# fpc.net
KiCad netlist of a schematic drawn in Altium Designer
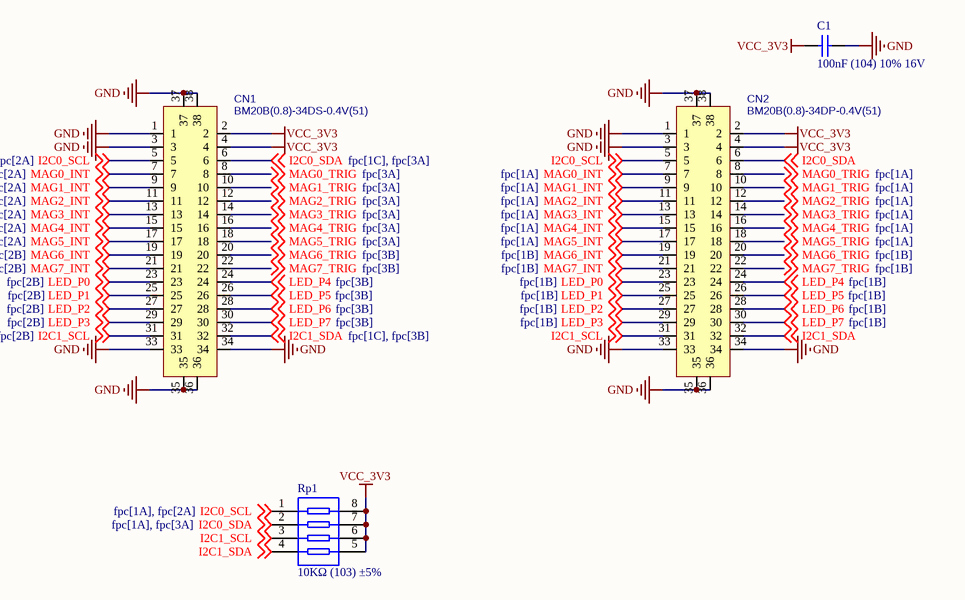
[diagram p0: fpc.SchDoc]

(export (version "E")
  (design (tool "Eeschema 10.0.6"))
  (components
    (comp (ref "C1")
      (value "100nF (104) 10% 16V")
      (footprint "LC-0402_C_NOSILK")
      (description "贴片电容")
      (libsource (lib "Miscellaneous Devices LC") (part "0402 100nF (104) 10% 16V"))
    )
    (comp (ref "CN1")
      (value "BM20B(0.8)-34DS-0.4V(51)")
      (footprint "CONN-SMD_34P-P0.40_BM20B-0.8-34DS-0.4V-51")
      (description "0.4mm BTB连接器-34P 母")
      (fields (field (name "BOM_SUPPLIER PART") "C424541") (field (name "CONTRIBUTOR") "LCSC"))
      (libsource (lib "merci") (part "BM20B(0.8)-34DS-0.4V(51)"))
    )
    (comp (ref "CN2")
      (value "BM20B(0.8)-34DP-0.4V(51)")
      (footprint "CONN-SMD_34P-P0.40_BM20B-0.8-34DP-0.4V-51")
      (description "0.4mm BTB连接器-34P 公")
      (fields (field (name "BOM_SUPPLIER PART") "C424540") (field (name "CONTRIBUTOR") "LCSC"))
      (libsource (lib "merci") (part "BM20B(0.8)-34DP-0.4V(51)"))
    )
    (comp (ref "Rp1")
      (value "10KΩ (103) ±5%")
      (footprint "0402_Rx4")
      (description "贴片排阻")
      (libsource (lib "Miscellaneous Devices LC") (part "0402*4 10KΩ (103) 5%"))
    )
  )
  (nets
    (net (code "1") (name "GND") (class "Default")
      (node (ref "C1") (pin "2") (pinfunction "2_2") (pintype "passive"))
      (node (ref "CN1") (pin "1") (pinfunction "1_1") (pintype "passive"))
      (node (ref "CN1") (pin "3") (pinfunction "3_3") (pintype "passive"))
      (node (ref "CN1") (pin "33") (pinfunction "33_33") (pintype "passive"))
      (node (ref "CN1") (pin "34") (pinfunction "34_34") (pintype "passive"))
      (node (ref "CN1") (pin "35") (pinfunction "35_35") (pintype "passive"))
      (node (ref "CN1") (pin "36") (pinfunction "36_36") (pintype "passive"))
      (node (ref "CN1") (pin "37") (pinfunction "37_37") (pintype "passive"))
      (node (ref "CN1") (pin "38") (pinfunction "38_38") (pintype "passive"))
      (node (ref "CN2") (pin "1") (pinfunction "1_1") (pintype "passive"))
      (node (ref "CN2") (pin "3") (pinfunction "3_3") (pintype "passive"))
      (node (ref "CN2") (pin "33") (pinfunction "33_33") (pintype "passive"))
      (node (ref "CN2") (pin "34") (pinfunction "34_34") (pintype "passive"))
      (node (ref "CN2") (pin "35") (pinfunction "35_35") (pintype "passive"))
      (node (ref "CN2") (pin "36") (pinfunction "36_36") (pintype "passive"))
      (node (ref "CN2") (pin "37") (pinfunction "37_37") (pintype "passive"))
      (node (ref "CN2") (pin "38") (pinfunction "38_38") (pintype "passive"))
    )
    (net (code "2") (name "I2C0_SCL") (class "Default")
      (node (ref "CN1") (pin "5") (pinfunction "5_5") (pintype "passive"))
      (node (ref "CN2") (pin "5") (pinfunction "5_5") (pintype "passive"))
      (node (ref "Rp1") (pin "1") (pinfunction "1_1") (pintype "passive"))
    )
    (net (code "3") (name "I2C0_SDA") (class "Default")
      (node (ref "CN1") (pin "6") (pinfunction "6_6") (pintype "passive"))
      (node (ref "CN2") (pin "6") (pinfunction "6_6") (pintype "passive"))
      (node (ref "Rp1") (pin "2") (pinfunction "2_2") (pintype "passive"))
    )
    (net (code "4") (name "I2C1_SCL") (class "Default")
      (node (ref "CN1") (pin "31") (pinfunction "31_31") (pintype "passive"))
      (node (ref "CN2") (pin "31") (pinfunction "31_31") (pintype "passive"))
      (node (ref "Rp1") (pin "3") (pinfunction "3_3") (pintype "passive"))
    )
    (net (code "5") (name "I2C1_SDA") (class "Default")
      (node (ref "CN1") (pin "32") (pinfunction "32_32") (pintype "passive"))
      (node (ref "CN2") (pin "32") (pinfunction "32_32") (pintype "passive"))
      (node (ref "Rp1") (pin "4") (pinfunction "4_4") (pintype "passive"))
    )
    (net (code "6") (name "LED_P0") (class "Default")
      (node (ref "CN1") (pin "23") (pinfunction "23_23") (pintype "passive"))
      (node (ref "CN2") (pin "23") (pinfunction "23_23") (pintype "passive"))
    )
    (net (code "7") (name "LED_P1") (class "Default")
      (node (ref "CN1") (pin "25") (pinfunction "25_25") (pintype "passive"))
      (node (ref "CN2") (pin "25") (pinfunction "25_25") (pintype "passive"))
    )
    (net (code "8") (name "LED_P2") (class "Default")
      (node (ref "CN1") (pin "27") (pinfunction "27_27") (pintype "passive"))
      (node (ref "CN2") (pin "27") (pinfunction "27_27") (pintype "passive"))
    )
    (net (code "9") (name "LED_P3") (class "Default")
      (node (ref "CN1") (pin "29") (pinfunction "29_29") (pintype "passive"))
      (node (ref "CN2") (pin "29") (pinfunction "29_29") (pintype "passive"))
    )
    (net (code "10") (name "LED_P4") (class "Default")
      (node (ref "CN1") (pin "24") (pinfunction "24_24") (pintype "passive"))
      (node (ref "CN2") (pin "24") (pinfunction "24_24") (pintype "passive"))
    )
    (net (code "11") (name "LED_P5") (class "Default")
      (node (ref "CN1") (pin "26") (pinfunction "26_26") (pintype "passive"))
      (node (ref "CN2") (pin "26") (pinfunction "26_26") (pintype "passive"))
    )
    (net (code "12") (name "LED_P6") (class "Default")
      (node (ref "CN1") (pin "28") (pinfunction "28_28") (pintype "passive"))
      (node (ref "CN2") (pin "28") (pinfunction "28_28") (pintype "passive"))
    )
    (net (code "13") (name "LED_P7") (class "Default")
      (node (ref "CN1") (pin "30") (pinfunction "30_30") (pintype "passive"))
      (node (ref "CN2") (pin "30") (pinfunction "30_30") (pintype "passive"))
    )
    (net (code "14") (name "MAG0_INT") (class "Default")
      (node (ref "CN1") (pin "7") (pinfunction "7_7") (pintype "passive"))
      (node (ref "CN2") (pin "7") (pinfunction "7_7") (pintype "passive"))
    )
    (net (code "15") (name "MAG0_TRIG") (class "Default")
      (node (ref "CN1") (pin "8") (pinfunction "8_8") (pintype "passive"))
      (node (ref "CN2") (pin "8") (pinfunction "8_8") (pintype "passive"))
    )
    (net (code "16") (name "MAG1_INT") (class "Default")
      (node (ref "CN1") (pin "9") (pinfunction "9_9") (pintype "passive"))
      (node (ref "CN2") (pin "9") (pinfunction "9_9") (pintype "passive"))
    )
    (net (code "17") (name "MAG1_TRIG") (class "Default")
      (node (ref "CN1") (pin "10") (pinfunction "10_10") (pintype "passive"))
      (node (ref "CN2") (pin "10") (pinfunction "10_10") (pintype "passive"))
    )
    (net (code "18") (name "MAG2_INT") (class "Default")
      (node (ref "CN1") (pin "11") (pinfunction "11_11") (pintype "passive"))
      (node (ref "CN2") (pin "11") (pinfunction "11_11") (pintype "passive"))
    )
    (net (code "19") (name "MAG2_TRIG") (class "Default")
      (node (ref "CN1") (pin "12") (pinfunction "12_12") (pintype "passive"))
      (node (ref "CN2") (pin "12") (pinfunction "12_12") (pintype "passive"))
    )
    (net (code "20") (name "MAG3_INT") (class "Default")
      (node (ref "CN1") (pin "13") (pinfunction "13_13") (pintype "passive"))
      (node (ref "CN2") (pin "13") (pinfunction "13_13") (pintype "passive"))
    )
    (net (code "21") (name "MAG3_TRIG") (class "Default")
      (node (ref "CN1") (pin "14") (pinfunction "14_14") (pintype "passive"))
      (node (ref "CN2") (pin "14") (pinfunction "14_14") (pintype "passive"))
    )
    (net (code "22") (name "MAG4_INT") (class "Default")
      (node (ref "CN1") (pin "15") (pinfunction "15_15") (pintype "passive"))
      (node (ref "CN2") (pin "15") (pinfunction "15_15") (pintype "passive"))
    )
    (net (code "23") (name "MAG4_TRIG") (class "Default")
      (node (ref "CN1") (pin "16") (pinfunction "16_16") (pintype "passive"))
      (node (ref "CN2") (pin "16") (pinfunction "16_16") (pintype "passive"))
    )
    (net (code "24") (name "MAG5_INT") (class "Default")
      (node (ref "CN1") (pin "17") (pinfunction "17_17") (pintype "passive"))
      (node (ref "CN2") (pin "17") (pinfunction "17_17") (pintype "passive"))
    )
    (net (code "25") (name "MAG5_TRIG") (class "Default")
      (node (ref "CN1") (pin "18") (pinfunction "18_18") (pintype "passive"))
      (node (ref "CN2") (pin "18") (pinfunction "18_18") (pintype "passive"))
    )
    (net (code "26") (name "MAG6_INT") (class "Default")
      (node (ref "CN1") (pin "19") (pinfunction "19_19") (pintype "passive"))
      (node (ref "CN2") (pin "19") (pinfunction "19_19") (pintype "passive"))
    )
    (net (code "27") (name "MAG6_TRIG") (class "Default")
      (node (ref "CN1") (pin "20") (pinfunction "20_20") (pintype "passive"))
      (node (ref "CN2") (pin "20") (pinfunction "20_20") (pintype "passive"))
    )
    (net (code "28") (name "MAG7_INT") (class "Default")
      (node (ref "CN1") (pin "21") (pinfunction "21_21") (pintype "passive"))
      (node (ref "CN2") (pin "21") (pinfunction "21_21") (pintype "passive"))
    )
    (net (code "29") (name "MAG7_TRIG") (class "Default")
      (node (ref "CN1") (pin "22") (pinfunction "22_22") (pintype "passive"))
      (node (ref "CN2") (pin "22") (pinfunction "22_22") (pintype "passive"))
    )
    (net (code "30") (name "VCC_3V3") (class "Default")
      (node (ref "C1") (pin "1") (pinfunction "1_1") (pintype "passive"))
      (node (ref "CN1") (pin "2") (pinfunction "2_2") (pintype "passive"))
      (node (ref "CN1") (pin "4") (pinfunction "4_4") (pintype "passive"))
      (node (ref "CN2") (pin "2") (pinfunction "2_2") (pintype "passive"))
      (node (ref "CN2") (pin "4") (pinfunction "4_4") (pintype "passive"))
      (node (ref "Rp1") (pin "5") (pinfunction "5_5") (pintype "passive"))
      (node (ref "Rp1") (pin "6") (pinfunction "6_6") (pintype "passive"))
      (node (ref "Rp1") (pin "7") (pinfunction "7_7") (pintype "passive"))
      (node (ref "Rp1") (pin "8") (pinfunction "8_8") (pintype "passive"))
    )
  )
)
